# samd21_actuatorhub_pro_1_0_1b_dec2023.net
KiCad netlist of a schematic drawn in EAGLE
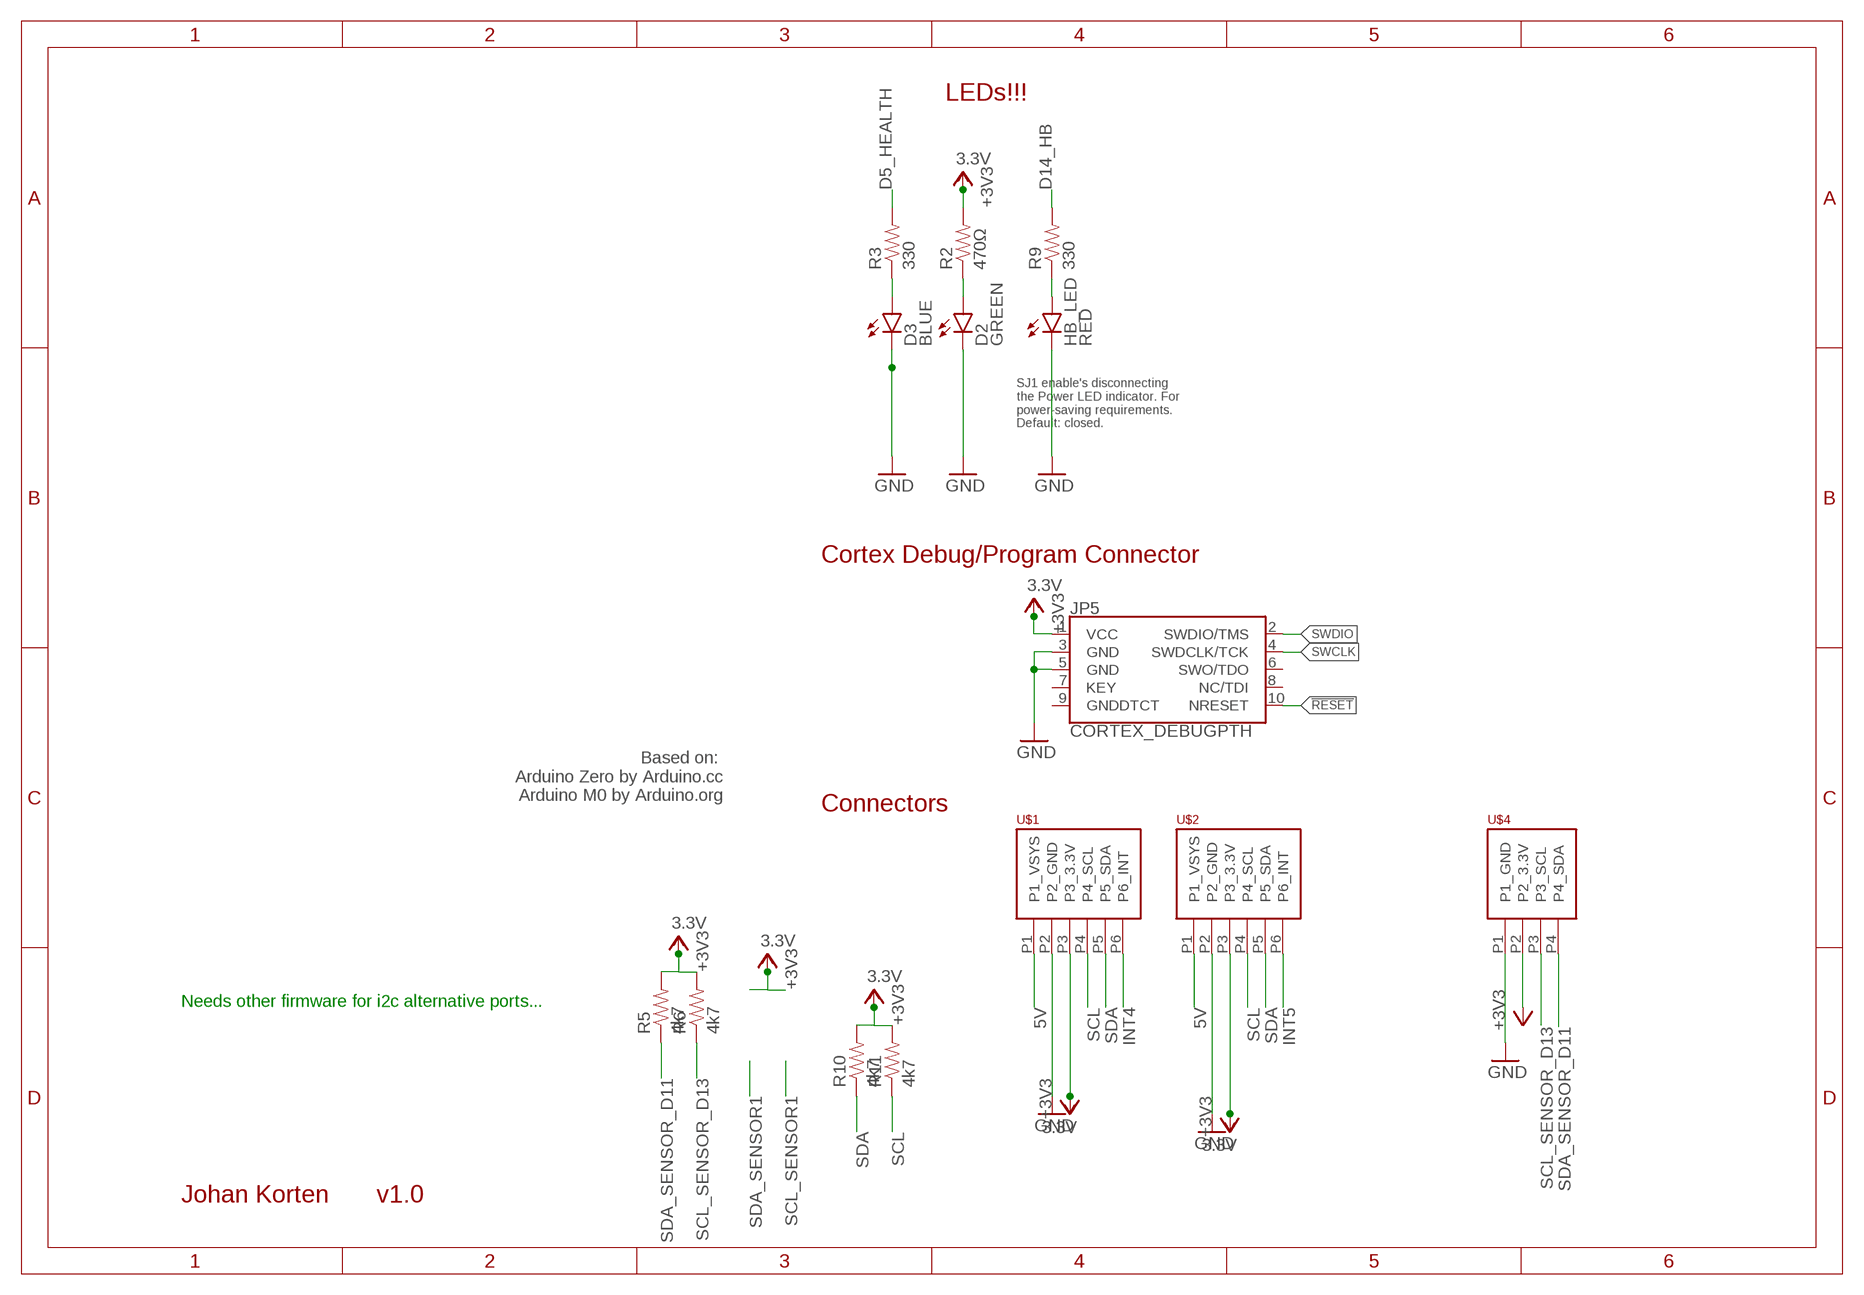
[diagram p0: schematic, sheet 1]
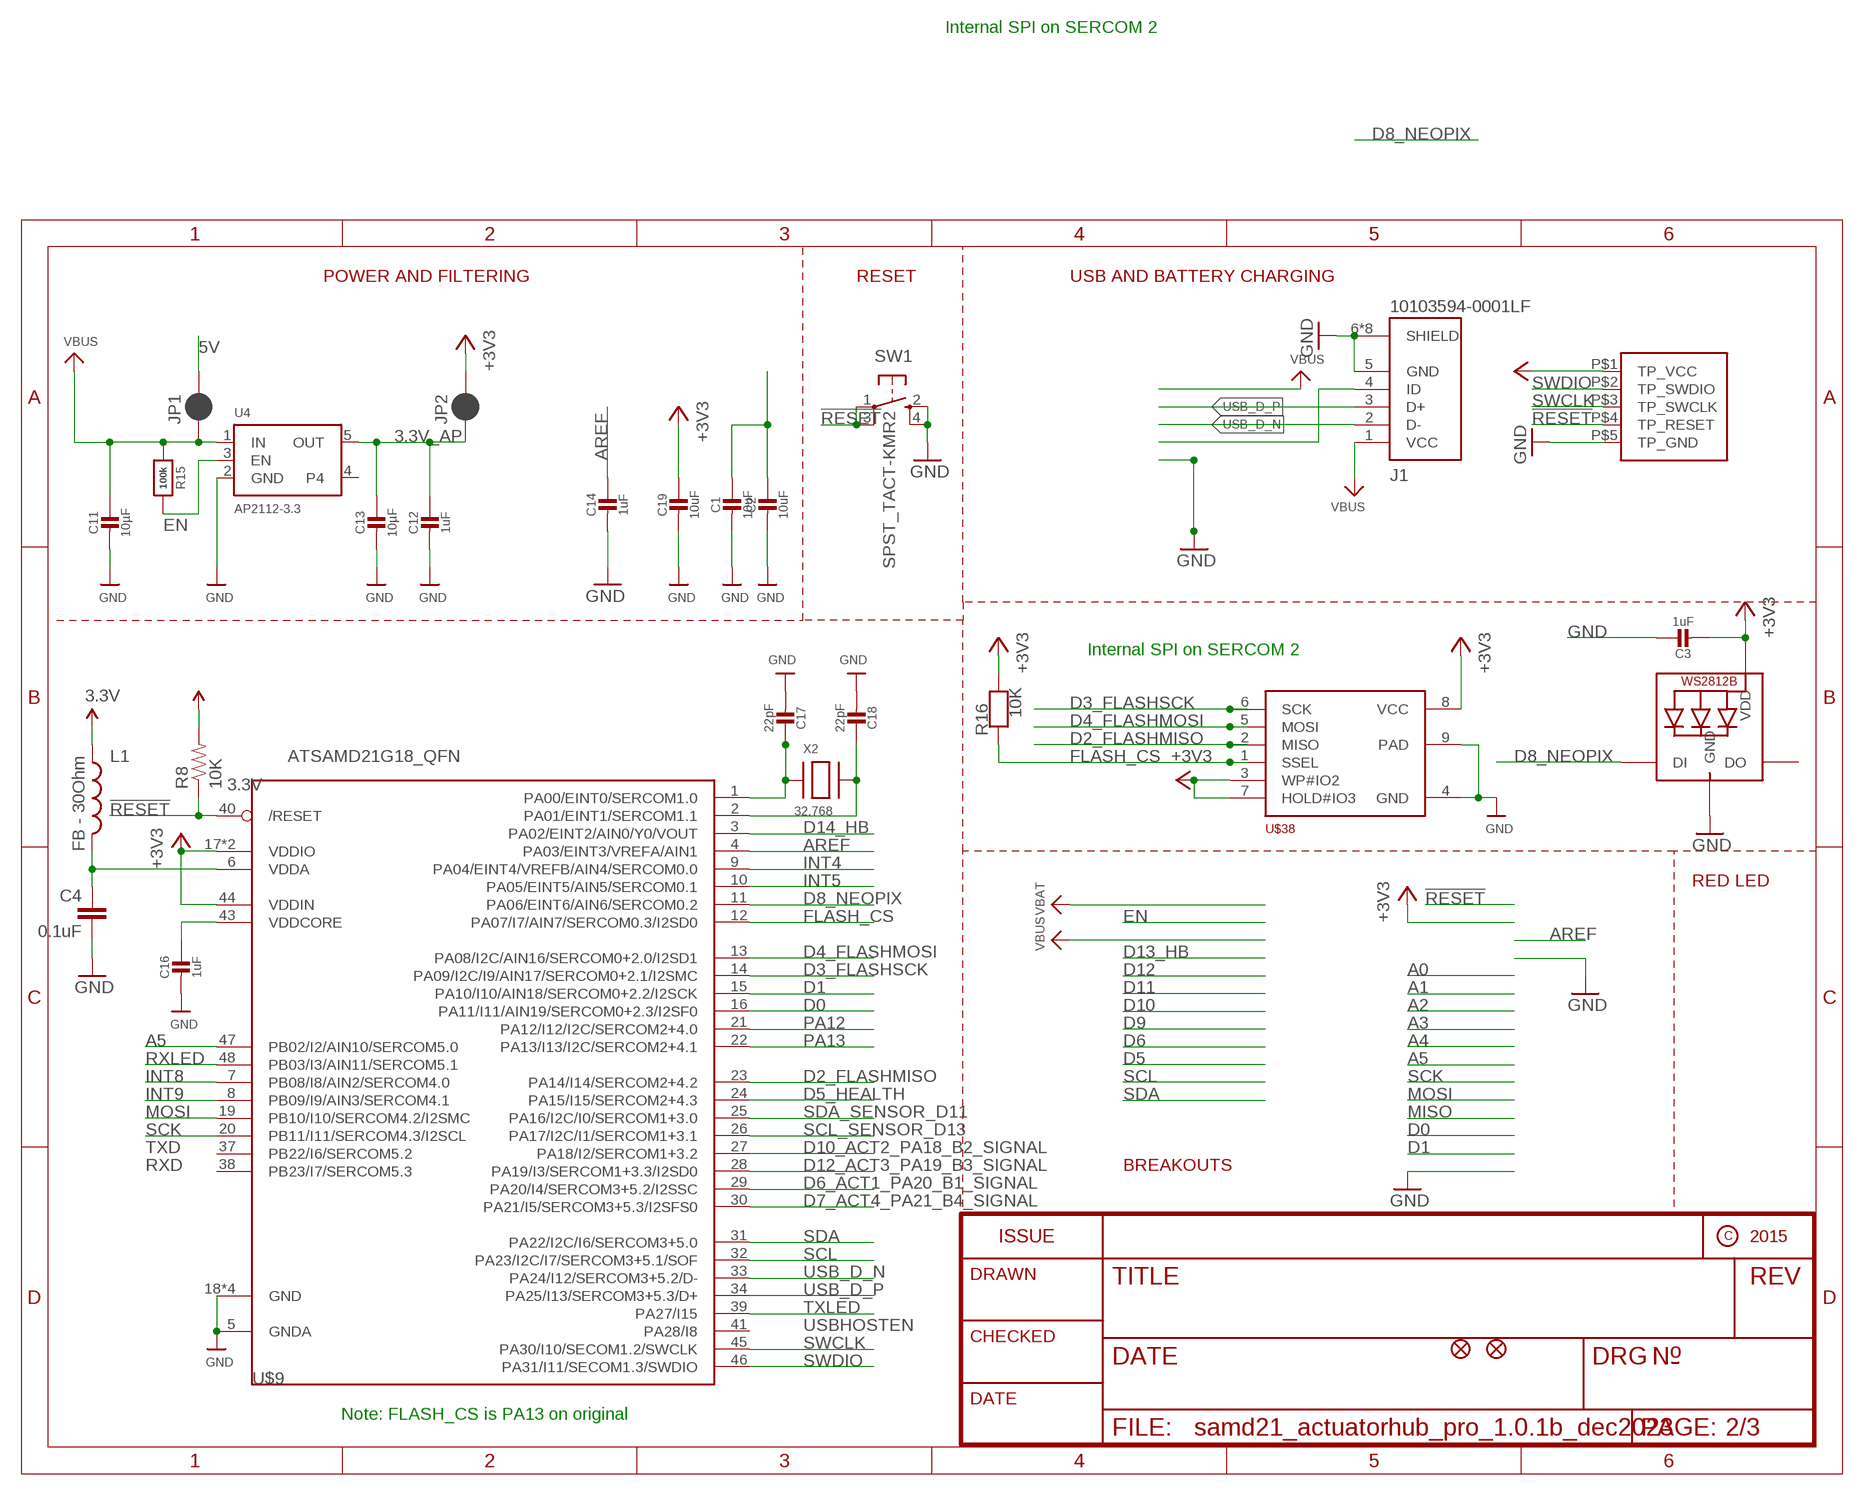
[diagram p1: schematic, sheet 2]
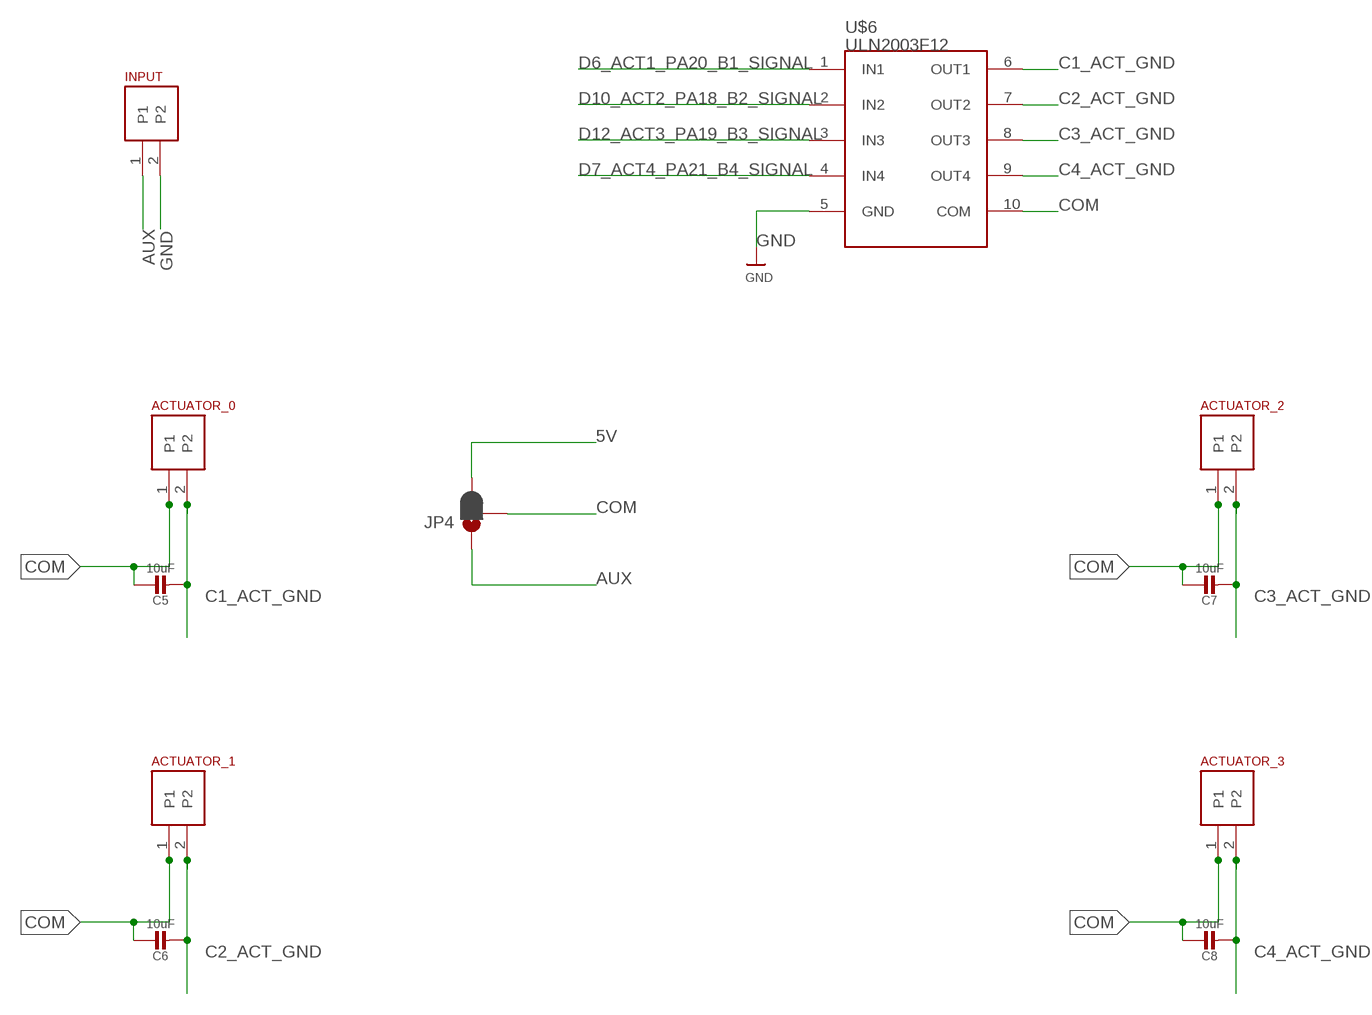
[diagram p2: schematic, sheet 3]

(export (version "E")
  (design (tool "Eeschema 10.0.6"))
  (components
    (comp (ref "ACTUATOR_0")
      (value "PHOENIX_PTSM_M2_TH")
      (footprint "eagle-import:PTSM_M2_THRHOLE")
      (libsource (lib "eagle-import") (part "PHOENIX_PTSM_M2_TH"))
    )
    (comp (ref "ACTUATOR_1")
      (value "PHOENIX_PTSM_M2_TH")
      (footprint "eagle-import:PTSM_M2_THRHOLE")
      (libsource (lib "eagle-import") (part "PHOENIX_PTSM_M2_TH"))
    )
    (comp (ref "ACTUATOR_2")
      (value "PHOENIX_PTSM_M2TH")
      (footprint "eagle-import:PTSM_M2_THRHOLE")
      (libsource (lib "eagle-import") (part "PHOENIX_PTSM_M2TH"))
    )
    (comp (ref "ACTUATOR_3")
      (value "PHOENIX_PTSM_M2TH")
      (footprint "eagle-import:PTSM_M2_THRHOLE")
      (libsource (lib "eagle-import") (part "PHOENIX_PTSM_M2TH"))
    )
    (comp (ref "C5")
      (value "10uF")
      (footprint "eagle-import:0805-NO")
      (libsource (lib "eagle-import") (part "CAP_CERAMIC0805-NOOUTLINE"))
    )
    (comp (ref "C6")
      (value "10uF")
      (footprint "eagle-import:0805-NO")
      (libsource (lib "eagle-import") (part "CAP_CERAMIC0805-NOOUTLINE"))
    )
    (comp (ref "C7")
      (value "10uF")
      (footprint "eagle-import:0805-NO")
      (libsource (lib "eagle-import") (part "CAP_CERAMIC0805-NOOUTLINE"))
    )
    (comp (ref "C8")
      (value "10uF")
      (footprint "eagle-import:0805-NO")
      (libsource (lib "eagle-import") (part "CAP_CERAMIC0805-NOOUTLINE"))
    )
    (comp (ref "INPUT")
      (value "PHOENIX_PTSM_M2_TH")
      (footprint "eagle-import:PTSM_M2_THRHOLE")
      (libsource (lib "eagle-import") (part "PHOENIX_PTSM_M2_TH"))
    )
    (comp (ref "JP4")
      (value "JUMPER-SMT_3_1-NC_PASTE_SILK")
      (footprint "eagle-import:SMT-JUMPER_3_1-NC_PASTE_SILK")
      (libsource (lib "eagle-import") (part "JUMPER-SMT_3_1-NC_PASTE_SILK"))
    )
    (comp (ref "U$6")
      (value "ULN2003F12")
      (footprint "eagle-import:U-DFN3030-10")
      (fields (field (name "MF") "Diodes Zetex"))
      (libsource (lib "eagle-import") (part "ULN2003F12"))
    )
    (comp (ref "D2")
      (value "GREEN")
      (footprint "eagle-import:LED-0603")
      (libsource (lib "eagle-import") (part "LED-RED0603"))
    )
    (comp (ref "D3")
      (value "BLUE")
      (footprint "eagle-import:LED-0603")
      (libsource (lib "eagle-import") (part "LED-BLUE0603"))
    )
    (comp (ref "HB_LED")
      (value "RED")
      (footprint "eagle-import:LED-0603")
      (libsource (lib "eagle-import") (part "LED-RED0603"))
    )
    (comp (ref "JP5")
      (value "CORTEX_DEBUGPTH")
      (footprint "eagle-import:2X5-PTH-1.27MM")
      (libsource (lib "eagle-import") (part "CORTEX_DEBUGPTH"))
    )
    (comp (ref "R2")
      (value "470Ω")
      (footprint "eagle-import:0603-RES")
      (libsource (lib "eagle-import") (part "330OHM1/10W1%(0603)"))
    )
    (comp (ref "R3")
      (value "330")
      (footprint "eagle-import:0603-RES")
      (libsource (lib "eagle-import") (part "330OHM1/10W1%(0603)"))
    )
    (comp (ref "R5")
      (value "4k7")
      (footprint "eagle-import:0603-RES")
      (libsource (lib "eagle-import") (part "330OHM1/10W1%(0603)"))
    )
    (comp (ref "R6")
      (value "4k7")
      (footprint "eagle-import:0603-RES")
      (libsource (lib "eagle-import") (part "330OHM1/10W1%(0603)"))
    )
    (comp (ref "R9")
      (value "330")
      (footprint "eagle-import:0603-RES")
      (libsource (lib "eagle-import") (part "330OHM1/10W1%(0603)"))
    )
    (comp (ref "R10")
      (value "4k7")
      (footprint "eagle-import:0603-RES")
      (libsource (lib "eagle-import") (part "330OHM1/10W1%(0603)"))
    )
    (comp (ref "R11")
      (value "4k7")
      (footprint "eagle-import:0603-RES")
      (libsource (lib "eagle-import") (part "330OHM1/10W1%(0603)"))
    )
    (comp (ref "U$1")
      (value "PHOENIX_PTSM_M6_TH_I2CPPANGLE")
      (footprint "eagle-import:PTSM_M6_THRHOLE")
      (libsource (lib "eagle-import") (part "PHOENIX_PTSM_M6_TH_I2CPPANGLE"))
    )
    (comp (ref "U$2")
      (value "PHOENIX_PTSM_M6_TH_I2CPPANGLE")
      (footprint "eagle-import:PTSM_M6_THRHOLE")
      (libsource (lib "eagle-import") (part "PHOENIX_PTSM_M6_TH_I2CPPANGLE"))
    )
    (comp (ref "U$4")
      (value "PHOENIX_PTSM_M4_THANGLE")
      (footprint "eagle-import:PTSM_M4_TH")
      (libsource (lib "eagle-import") (part "PHOENIX_PTSM_M4_THANGLE"))
    )
    (comp (ref "C1")
      (value "10uF")
      (footprint "eagle-import:0805-NO")
      (libsource (lib "eagle-import") (part "CAP_CERAMIC0805-NOOUTLINE"))
    )
    (comp (ref "C2")
      (value "10uF")
      (footprint "eagle-import:0805-NO")
      (libsource (lib "eagle-import") (part "CAP_CERAMIC0805-NOOUTLINE"))
    )
    (comp (ref "C3")
      (value "1uF")
      (footprint "eagle-import:0603-NO")
      (libsource (lib "eagle-import") (part "CAP_CERAMIC0603_NO"))
    )
    (comp (ref "C4")
      (value "0.1uF")
      (footprint "eagle-import:0402-CAP")
      (libsource (lib "eagle-import") (part "0.1UF-16V(+-10%)(0402)"))
    )
    (comp (ref "C11")
      (value "10µF")
      (footprint "eagle-import:0805-NO")
      (libsource (lib "eagle-import") (part "CAP_CERAMIC0805-NOOUTLINE"))
    )
    (comp (ref "C12")
      (value "1uF")
      (footprint "eagle-import:0603-NO")
      (libsource (lib "eagle-import") (part "CAP_CERAMIC0603_NO"))
    )
    (comp (ref "C13")
      (value "10µF")
      (footprint "eagle-import:0805-NO")
      (libsource (lib "eagle-import") (part "CAP_CERAMIC0805-NOOUTLINE"))
    )
    (comp (ref "C14")
      (value "1uF")
      (footprint "eagle-import:0603-NO")
      (libsource (lib "eagle-import") (part "CAP_CERAMIC0603_NO"))
    )
    (comp (ref "C16")
      (value "1uF")
      (footprint "eagle-import:0603-NO")
      (libsource (lib "eagle-import") (part "CAP_CERAMIC0603_NO"))
    )
    (comp (ref "C17")
      (value "22pF")
      (footprint "eagle-import:0603-NO")
      (libsource (lib "eagle-import") (part "CAP_CERAMIC0603_NO"))
    )
    (comp (ref "C18")
      (value "22pF")
      (footprint "eagle-import:0603-NO")
      (libsource (lib "eagle-import") (part "CAP_CERAMIC0603_NO"))
    )
    (comp (ref "C19")
      (value "10uF")
      (footprint "eagle-import:0805-NO")
      (libsource (lib "eagle-import") (part "CAP_CERAMIC0805-NOOUTLINE"))
    )
    (comp (ref "J1")
      (value "10103594-0001LF")
      (footprint "eagle-import:AMPHENOL_10103594-0001LF")
      (fields (field (name "MF") "AMPHENOL ICC / FCI"))
      (libsource (lib "eagle-import") (part "10103594-0001LF"))
    )
    (comp (ref "JP1")
      (value "JUMPER-SMT_2_NC_PASTE_SILK")
      (footprint "eagle-import:SMT-JUMPER_2_NC_PASTE_SILK")
      (libsource (lib "eagle-import") (part "JUMPER-SMT_2_NC_PASTE_SILK"))
    )
    (comp (ref "JP2")
      (value "JUMPER-SMT_2_NC_PASTE_SILK")
      (footprint "eagle-import:SMT-JUMPER_2_NC_PASTE_SILK")
      (libsource (lib "eagle-import") (part "JUMPER-SMT_2_NC_PASTE_SILK"))
    )
    (comp (ref "L1")
      (value "FB - 30Ohm")
      (footprint "eagle-import:0603")
      (libsource (lib "eagle-import") (part "INDUCTOR0603"))
    )
    (comp (ref "LED1")
      (value "WS2812B3535")
      (footprint "eagle-import:LED3535")
      (libsource (lib "eagle-import") (part "WS2812B3535"))
    )
    (comp (ref "R8")
      (value "10K")
      (footprint "eagle-import:0603-RES")
      (libsource (lib "eagle-import") (part "10KOHM-1/10W-1%(0603)0603"))
    )
    (comp (ref "R15")
      (value "100k")
      (footprint "eagle-import:0603-NO")
      (libsource (lib "eagle-import") (part "RESISTOR_0603_NOOUT"))
    )
    (comp (ref "R16")
      (value "10K")
      (footprint "eagle-import:0603-NO")
      (libsource (lib "eagle-import") (part "RESISTOR_0603_NOOUT"))
    )
    (comp (ref "SW1")
      (value "SPST_TACT-KMR2")
      (footprint "eagle-import:KMR2")
      (libsource (lib "eagle-import") (part "SPST_TACT-KMR2"))
    )
    (comp (ref "U$5")
      (value "HUB_TESTPINSHUBS")
      (footprint "eagle-import:TEST_PINS")
      (libsource (lib "eagle-import") (part "HUB_TESTPINSHUBS"))
    )
    (comp (ref "U$9")
      (value "ATSAMD21G18_QFN")
      (footprint "eagle-import:TQFN48_7MM")
      (libsource (lib "eagle-import") (part "ATSAMD21G_QFN"))
    )
    (comp (ref "U$34")
      (value "FIDUCIAL\"\"")
      (footprint "eagle-import:FIDUCIAL_1MM")
      (libsource (lib "eagle-import") (part "FIDUCIAL{dblquote}{dblquote}"))
    )
    (comp (ref "U$35")
      (value "FIDUCIAL\"\"")
      (footprint "eagle-import:FIDUCIAL_1MM")
      (libsource (lib "eagle-import") (part "FIDUCIAL{dblquote}{dblquote}"))
    )
    (comp (ref "U$38")
      (value "S25FL064LABNFI040")
      (footprint "eagle-import:SON80P400X400X60-9N")
      (libsource (lib "eagle-import") (part "S25FL064LABNFI040"))
    )
    (comp (ref "U4")
      (value "AP2112-3.3")
      (footprint "eagle-import:SOT23-5")
      (libsource (lib "eagle-import") (part "VREG_SOT23-5"))
    )
    (comp (ref "X2")
      (value "32.768")
      (footprint "eagle-import:XTAL3215")
      (libsource (lib "eagle-import") (part "XTAL-3.2X1.5"))
    )
  )
  (nets
    (net (code "1") (name "+3V3") (class "Default")
      (node (ref "C19") (pin "1") (pinfunction "1_1") (pintype "passive"))
      (node (ref "C3") (pin "2") (pinfunction "2_2") (pintype "passive"))
      (node (ref "JP2") (pin "2") (pinfunction "2_2") (pintype "passive"))
      (node (ref "JP5") (pin "1") (pinfunction "VCC_1") (pintype "bidirectional"))
      (node (ref "L1") (pin "1") (pinfunction "1_1") (pintype "passive"))
      (node (ref "LED1") (pin "2") (pinfunction "VDD_2") (pintype "power_in"))
      (node (ref "R10") (pin "2") (pinfunction "2_2") (pintype "passive"))
      (node (ref "R11") (pin "2") (pinfunction "2_2") (pintype "passive"))
      (node (ref "R16") (pin "2") (pinfunction "2_2") (pintype "passive"))
      (node (ref "R2") (pin "2") (pinfunction "2_2") (pintype "passive"))
      (node (ref "R5") (pin "2") (pinfunction "2_2") (pintype "passive"))
      (node (ref "R6") (pin "2") (pinfunction "2_2") (pintype "passive"))
      (node (ref "R8") (pin "2") (pinfunction "2_2") (pintype "passive"))
      (node (ref "U$1") (pin "P3") (pinfunction "P3_3.3V_P3") (pintype "power_in"))
      (node (ref "U$2") (pin "P3") (pinfunction "P3_3.3V_P3") (pintype "power_in"))
      (node (ref "U$38") (pin "3") (pinfunction "WP#IO2_3") (pintype "bidirectional"))
      (node (ref "U$38") (pin "7") (pinfunction "HOLD#IO3_7") (pintype "bidirectional"))
      (node (ref "U$38") (pin "8") (pinfunction "VCC_8") (pintype "bidirectional"))
      (node (ref "U$4") (pin "P2") (pinfunction "P2_3.3V_P2") (pintype "power_in"))
      (node (ref "U$5") (pin "P$1") (pinfunction "TP_VCC_P$1") (pintype "bidirectional"))
      (node (ref "U$9") (pin "17") (pinfunction "VDDIO_17") (pintype "power_in"))
      (node (ref "U$9") (pin "36") (pinfunction "VDDIO_36") (pintype "power_in"))
      (node (ref "U$9") (pin "44") (pinfunction "VDDIN_44") (pintype "power_in"))
    )
    (net (code "2") (name "3.3V_AP") (class "Default")
      (node (ref "C12") (pin "1") (pinfunction "1_1") (pintype "passive"))
      (node (ref "C13") (pin "1") (pinfunction "1_1") (pintype "passive"))
      (node (ref "JP2") (pin "1") (pinfunction "1_1") (pintype "passive"))
      (node (ref "U4") (pin "5") (pinfunction "OUT_5") (pintype "power_in"))
    )
    (net (code "3") (name "5V") (class "Default")
      (node (ref "C1") (pin "1") (pinfunction "1_1") (pintype "passive"))
      (node (ref "C2") (pin "1") (pinfunction "1_1") (pintype "passive"))
      (node (ref "JP1") (pin "2") (pinfunction "2_2") (pintype "passive"))
      (node (ref "JP4") (pin "3") (pinfunction "3_3") (pintype "passive"))
      (node (ref "U$1") (pin "P1") (pinfunction "P1_VSYS_P1") (pintype "power_in"))
      (node (ref "U$2") (pin "P1") (pinfunction "P1_VSYS_P1") (pintype "power_in"))
    )
    (net (code "9") (name "A5") (class "Default")
      (node (ref "U$9") (pin "47") (pinfunction "PB02/I2/AIN10/SERCOM5.0_47") (pintype "bidirectional"))
    )
    (net (code "10") (name "AREF") (class "Default")
      (node (ref "C14") (pin "1") (pinfunction "1_1") (pintype "passive"))
      (node (ref "U$9") (pin "4") (pinfunction "PA03/EINT3/VREFA/AIN1_4") (pintype "bidirectional"))
    )
    (net (code "11") (name "AUX") (class "Default")
      (node (ref "INPUT") (pin "1") (pinfunction "P1_1") (pintype "bidirectional"))
      (node (ref "JP4") (pin "1") (pinfunction "1_1") (pintype "passive"))
    )
    (net (code "12") (name "C1_ACT_GND") (class "Default")
      (node (ref "ACTUATOR_0") (pin "2") (pinfunction "P2_2") (pintype "bidirectional"))
      (node (ref "C5") (pin "2") (pinfunction "2_2") (pintype "passive"))
      (node (ref "U$6") (pin "6") (pinfunction "OUT1_6") (pintype "bidirectional"))
    )
    (net (code "13") (name "C2_ACT_GND") (class "Default")
      (node (ref "ACTUATOR_1") (pin "2") (pinfunction "P2_2") (pintype "bidirectional"))
      (node (ref "C6") (pin "2") (pinfunction "2_2") (pintype "passive"))
      (node (ref "U$6") (pin "7") (pinfunction "OUT2_7") (pintype "bidirectional"))
    )
    (net (code "14") (name "C3_ACT_GND") (class "Default")
      (node (ref "ACTUATOR_2") (pin "2") (pinfunction "P2_2") (pintype "bidirectional"))
      (node (ref "C7") (pin "2") (pinfunction "2_2") (pintype "passive"))
      (node (ref "U$6") (pin "8") (pinfunction "OUT3_8") (pintype "bidirectional"))
    )
    (net (code "15") (name "C4_ACT_GND") (class "Default")
      (node (ref "ACTUATOR_3") (pin "2") (pinfunction "P2_2") (pintype "bidirectional"))
      (node (ref "C8") (pin "2") (pinfunction "2_2") (pintype "passive"))
      (node (ref "U$6") (pin "9") (pinfunction "OUT4_9") (pintype "bidirectional"))
    )
    (net (code "16") (name "COM") (class "Default")
      (node (ref "ACTUATOR_0") (pin "1") (pinfunction "P1_1") (pintype "bidirectional"))
      (node (ref "ACTUATOR_1") (pin "1") (pinfunction "P1_1") (pintype "bidirectional"))
      (node (ref "ACTUATOR_2") (pin "1") (pinfunction "P1_1") (pintype "bidirectional"))
      (node (ref "ACTUATOR_3") (pin "1") (pinfunction "P1_1") (pintype "bidirectional"))
      (node (ref "C5") (pin "1") (pinfunction "1_1") (pintype "passive"))
      (node (ref "C6") (pin "1") (pinfunction "1_1") (pintype "passive"))
      (node (ref "C7") (pin "1") (pinfunction "1_1") (pintype "passive"))
      (node (ref "C8") (pin "1") (pinfunction "1_1") (pintype "passive"))
      (node (ref "JP4") (pin "2") (pinfunction "2_2") (pintype "passive"))
      (node (ref "U$6") (pin "10") (pinfunction "COM_10") (pintype "bidirectional"))
    )
    (net (code "17") (name "D0") (class "Default")
      (node (ref "U$9") (pin "16") (pinfunction "PA11/I11/AIN19/SERCOM0+2.3/I2SF0_16") (pintype "bidirectional"))
    )
    (net (code "18") (name "D1") (class "Default")
      (node (ref "U$9") (pin "15") (pinfunction "PA10/I10/AIN18/SERCOM0+2.2/I2SCK_15") (pintype "bidirectional"))
    )
    (net (code "19") (name "D2_FLASHMISO") (class "Default")
      (node (ref "U$38") (pin "2") (pinfunction "MISO_2") (pintype "bidirectional"))
      (node (ref "U$9") (pin "23") (pinfunction "PA14/I14/SERCOM2+4.2_23") (pintype "bidirectional"))
    )
    (net (code "20") (name "D3_FLASHSCK") (class "Default")
      (node (ref "U$38") (pin "6") (pinfunction "SCK_6") (pintype "bidirectional"))
      (node (ref "U$9") (pin "14") (pinfunction "PA09/I2C/I9/AIN17/SERCOM0+2.1/I2SMC_14") (pintype "bidirectional"))
    )
    (net (code "21") (name "D4_FLASHMOSI") (class "Default")
      (node (ref "U$38") (pin "5") (pinfunction "MOSI_5") (pintype "bidirectional"))
      (node (ref "U$9") (pin "13") (pinfunction "PA08/I2C/AIN16/SERCOM0+2.0/I2SD1_13") (pintype "bidirectional"))
    )
    (net (code "23") (name "D5_HEALTH") (class "Default")
      (node (ref "R3") (pin "2") (pinfunction "2_2") (pintype "passive"))
      (node (ref "U$9") (pin "24") (pinfunction "PA15/I15/SERCOM2+4.3_24") (pintype "bidirectional"))
    )
    (net (code "25") (name "D6_ACT1_PA20_B1_SIGNAL") (class "Default")
      (node (ref "U$6") (pin "1") (pinfunction "IN1_1") (pintype "bidirectional"))
      (node (ref "U$9") (pin "29") (pinfunction "PA20/I4/SERCOM3+5.2/I2SSC_29") (pintype "bidirectional"))
    )
    (net (code "26") (name "D7_ACT4_PA21_B4_SIGNAL") (class "Default")
      (node (ref "U$6") (pin "4") (pinfunction "IN4_4") (pintype "bidirectional"))
      (node (ref "U$9") (pin "30") (pinfunction "PA21/I5/SERCOM3+5.3/I2SFS0_30") (pintype "bidirectional"))
    )
    (net (code "27") (name "D8_NEOPIX") (class "Default")
      (node (ref "LED1") (pin "1") (pinfunction "DI_1") (pintype "input"))
      (node (ref "U$9") (pin "11") (pinfunction "PA06/EINT6/AIN6/SERCOM0.2_11") (pintype "bidirectional"))
    )
    (net (code "30") (name "D10_ACT2_PA18_B2_SIGNAL") (class "Default")
      (node (ref "U$6") (pin "2") (pinfunction "IN2_2") (pintype "bidirectional"))
      (node (ref "U$9") (pin "27") (pinfunction "PA18/I2/SERCOM1+3.2_27") (pintype "bidirectional"))
    )
    (net (code "33") (name "D12_ACT3_PA19_B3_SIGNAL") (class "Default")
      (node (ref "U$6") (pin "3") (pinfunction "IN3_3") (pintype "bidirectional"))
      (node (ref "U$9") (pin "28") (pinfunction "PA19/I3/SERCOM1+3.3/I2SD0_28") (pintype "bidirectional"))
    )
    (net (code "35") (name "D14_HB") (class "Default")
      (node (ref "R9") (pin "2") (pinfunction "2_2") (pintype "passive"))
      (node (ref "U$9") (pin "3") (pinfunction "PA02/EINT2/AIN0/Y0/VOUT_3") (pintype "bidirectional"))
    )
    (net (code "36") (name "EN") (class "Default")
      (node (ref "R15") (pin "2") (pinfunction "2_2") (pintype "passive"))
      (node (ref "U4") (pin "3") (pinfunction "EN_3") (pintype "input"))
    )
    (net (code "37") (name "FLASH_CS") (class "Default")
      (node (ref "R16") (pin "1") (pinfunction "1_1") (pintype "passive"))
      (node (ref "U$38") (pin "1") (pinfunction "SSEL_1") (pintype "bidirectional"))
      (node (ref "U$9") (pin "12") (pinfunction "PA07/I7/AIN7/SERCOM0.3/I2SD0_12") (pintype "bidirectional"))
    )
    (net (code "38") (name "GND") (class "Default")
      (node (ref "C1") (pin "2") (pinfunction "2_2") (pintype "passive"))
      (node (ref "C11") (pin "2") (pinfunction "2_2") (pintype "passive"))
      (node (ref "C12") (pin "2") (pinfunction "2_2") (pintype "passive"))
      (node (ref "C13") (pin "2") (pinfunction "2_2") (pintype "passive"))
      (node (ref "C14") (pin "2") (pinfunction "2_2") (pintype "passive"))
      (node (ref "C16") (pin "2") (pinfunction "2_2") (pintype "passive"))
      (node (ref "C17") (pin "2") (pinfunction "2_2") (pintype "passive"))
      (node (ref "C18") (pin "2") (pinfunction "2_2") (pintype "passive"))
      (node (ref "C19") (pin "2") (pinfunction "2_2") (pintype "passive"))
      (node (ref "C2") (pin "2") (pinfunction "2_2") (pintype "passive"))
      (node (ref "C3") (pin "1") (pinfunction "1_1") (pintype "passive"))
      (node (ref "C4") (pin "2") (pinfunction "2_2") (pintype "passive"))
      (node (ref "D2") (pin "C") (pinfunction "C_C") (pintype "passive"))
      (node (ref "D3") (pin "C") (pinfunction "C_C") (pintype "passive"))
      (node (ref "HB_LED") (pin "C") (pinfunction "C_C") (pintype "passive"))
      (node (ref "INPUT") (pin "2") (pinfunction "P2_2") (pintype "bidirectional"))
      (node (ref "J1") (pin "10") (pinfunction "SHIELD_10") (pintype "passive"))
      (node (ref "J1") (pin "11") (pinfunction "SHIELD_11") (pintype "passive"))
      (node (ref "J1") (pin "5") (pinfunction "GND_5") (pintype "power_in"))
      (node (ref "J1") (pin "6") (pinfunction "SHIELD_6") (pintype "passive"))
      (node (ref "J1") (pin "7") (pinfunction "SHIELD_7") (pintype "passive"))
      (node (ref "J1") (pin "8") (pinfunction "SHIELD_8") (pintype "passive"))
      (node (ref "J1") (pin "9") (pinfunction "SHIELD_9") (pintype "passive"))
      (node (ref "J1") (pin "S1") (pinfunction "SHIELD_S1") (pintype "passive"))
      (node (ref "J1") (pin "S2") (pinfunction "SHIELD_S2") (pintype "passive"))
      (node (ref "JP5") (pin "3") (pinfunction "GND_3") (pintype "bidirectional"))
      (node (ref "JP5") (pin "5") (pinfunction "GND_5") (pintype "bidirectional"))
      (node (ref "LED1") (pin "4") (pinfunction "GND_4") (pintype "power_in"))
      (node (ref "SW1") (pin "2") (pinfunction "S_2") (pintype "passive"))
      (node (ref "SW1") (pin "4") (pinfunction "S1_4") (pintype "passive"))
      (node (ref "U$1") (pin "P2") (pinfunction "P2_GND_P2") (pintype "power_in"))
      (node (ref "U$2") (pin "P2") (pinfunction "P2_GND_P2") (pintype "power_in"))
      (node (ref "U$38") (pin "4") (pinfunction "GND_4") (pintype "bidirectional"))
      (node (ref "U$38") (pin "9") (pinfunction "PAD_9") (pintype "bidirectional"))
      (node (ref "U$4") (pin "P1") (pinfunction "P1_GND_P1") (pintype "power_in"))
      (node (ref "U$5") (pin "P$5") (pinfunction "TP_GND_P$5") (pintype "bidirectional"))
      (node (ref "U$6") (pin "5") (pinfunction "GND_5") (pintype "bidirectional"))
      (node (ref "U$9") (pin "18") (pinfunction "GND_18") (pintype "power_in"))
      (node (ref "U$9") (pin "35") (pinfunction "GND_35") (pintype "power_in"))
      (node (ref "U$9") (pin "42") (pinfunction "GND_42") (pintype "power_in"))
      (node (ref "U$9") (pin "5") (pinfunction "GNDA_5") (pintype "power_in"))
      (node (ref "U$9") (pin "THERMAL") (pinfunction "GND_THERMAL") (pintype "power_in"))
      (node (ref "U4") (pin "2") (pinfunction "GND_2") (pintype "power_in"))
    )
    (net (code "39") (name "INT4") (class "Default")
      (node (ref "U$1") (pin "P6") (pinfunction "P6_INT_P6") (pintype "power_in"))
      (node (ref "U$9") (pin "9") (pinfunction "PA04/EINT4/VREFB/AIN4/SERCOM0.0_9") (pintype "bidirectional"))
    )
    (net (code "40") (name "INT5") (class "Default")
      (node (ref "U$2") (pin "P6") (pinfunction "P6_INT_P6") (pintype "power_in"))
      (node (ref "U$9") (pin "10") (pinfunction "PA05/EINT5/AIN5/SERCOM0.1_10") (pintype "bidirectional"))
    )
    (net (code "41") (name "INT8") (class "Default")
      (node (ref "U$9") (pin "7") (pinfunction "PB08/I8/AIN2/SERCOM4.0_7") (pintype "bidirectional"))
    )
    (net (code "42") (name "INT9") (class "Default")
      (node (ref "U$9") (pin "8") (pinfunction "PB09/I9/AIN3/SERCOM4.1_8") (pintype "bidirectional"))
    )
    (net (code "44") (name "MOSI") (class "Default")
      (node (ref "U$9") (pin "19") (pinfunction "PB10/I10/SERCOM4.2/I2SMC_19") (pintype "bidirectional"))
    )
    (net (code "45") (name "Net-(D2-PadA)") (class "Default")
      (node (ref "D2") (pin "A") (pinfunction "A_A") (pintype "passive"))
      (node (ref "R2") (pin "1") (pinfunction "1_1") (pintype "passive"))
    )
    (net (code "46") (name "Net-(D3-PadA)") (class "Default")
      (node (ref "D3") (pin "A") (pinfunction "A_A") (pintype "passive"))
      (node (ref "R3") (pin "1") (pinfunction "1_1") (pintype "passive"))
    )
    (net (code "47") (name "Net-(HB_LED-PadA)") (class "Default")
      (node (ref "HB_LED") (pin "A") (pinfunction "A_A") (pintype "passive"))
      (node (ref "R9") (pin "1") (pinfunction "1_1") (pintype "passive"))
    )
    (net (code "48") (name "Net-(U$9-PA00{slash}EINT0{slash}SERCOM1.0)") (class "Default")
      (node (ref "C17") (pin "1") (pinfunction "1_1") (pintype "passive"))
      (node (ref "U$9") (pin "1") (pinfunction "PA00/EINT0/SERCOM1.0_1") (pintype "bidirectional"))
      (node (ref "X2") (pin "P$1") (pinfunction "P$1_P$1") (pintype "bidirectional"))
    )
    (net (code "49") (name "Net-(U$9-PA01{slash}EINT1{slash}SERCOM1.1)") (class "Default")
      (node (ref "C18") (pin "1") (pinfunction "1_1") (pintype "passive"))
      (node (ref "U$9") (pin "2") (pinfunction "PA01/EINT1/SERCOM1.1_2") (pintype "bidirectional"))
      (node (ref "X2") (pin "P$2") (pinfunction "P$2_P$2") (pintype "bidirectional"))
    )
    (net (code "50") (name "Net-(U$9-VDDA)") (class "Default")
      (node (ref "C4") (pin "1") (pinfunction "1_1") (pintype "passive"))
      (node (ref "L1") (pin "2") (pinfunction "2_2") (pintype "passive"))
      (node (ref "U$9") (pin "6") (pinfunction "VDDA_6") (pintype "power_in"))
    )
    (net (code "51") (name "Net-(U$9-VDDCORE)") (class "Default")
      (node (ref "C16") (pin "1") (pinfunction "1_1") (pintype "passive"))
      (node (ref "U$9") (pin "43") (pinfunction "VDDCORE_43") (pintype "power_in"))
    )
    (net (code "52") (name "PA12") (class "Default")
      (node (ref "U$9") (pin "21") (pinfunction "PA12/I12/I2C/SERCOM2+4.0_21") (pintype "bidirectional"))
    )
    (net (code "53") (name "PA13") (class "Default")
      (node (ref "U$9") (pin "22") (pinfunction "PA13/I13/I2C/SERCOM2+4.1_22") (pintype "bidirectional"))
    )
    (net (code "54") (name "RXLED") (class "Default")
      (node (ref "U$9") (pin "48") (pinfunction "PB03/I3/AIN11/SERCOM5.1_48") (pintype "bidirectional"))
    )
    (net (code "55") (name "SCK") (class "Default")
      (node (ref "U$9") (pin "20") (pinfunction "PB11/I11/SERCOM4.3/I2SCL_20") (pintype "bidirectional"))
    )
    (net (code "56") (name "SCL") (class "Default")
      (node (ref "R11") (pin "1") (pinfunction "1_1") (pintype "passive"))
      (node (ref "U$1") (pin "P4") (pinfunction "P4_SCL_P4") (pintype "bidirectional"))
      (node (ref "U$2") (pin "P4") (pinfunction "P4_SCL_P4") (pintype "bidirectional"))
      (node (ref "U$9") (pin "32") (pinfunction "PA23/I2C/I7/SERCOM3+5.1/SOF_32") (pintype "bidirectional"))
    )
    (net (code "58") (name "SCL_SENSOR_D13") (class "Default")
      (node (ref "R6") (pin "1") (pinfunction "1_1") (pintype "passive"))
      (node (ref "U$4") (pin "P3") (pinfunction "P3_SCL_P3") (pintype "bidirectional"))
      (node (ref "U$9") (pin "26") (pinfunction "PA17/I2C/I1/SERCOM1+3.1_26") (pintype "bidirectional"))
    )
    (net (code "59") (name "SDA") (class "Default")
      (node (ref "R10") (pin "1") (pinfunction "1_1") (pintype "passive"))
      (node (ref "U$1") (pin "P5") (pinfunction "P5_SDA_P5") (pintype "bidirectional"))
      (node (ref "U$2") (pin "P5") (pinfunction "P5_SDA_P5") (pintype "bidirectional"))
      (node (ref "U$9") (pin "31") (pinfunction "PA22/I2C/I6/SERCOM3+5.0_31") (pintype "bidirectional"))
    )
    (net (code "61") (name "SDA_SENSOR_D11") (class "Default")
      (node (ref "R5") (pin "1") (pinfunction "1_1") (pintype "passive"))
      (node (ref "U$4") (pin "P4") (pinfunction "P4_SDA_P4") (pintype "bidirectional"))
      (node (ref "U$9") (pin "25") (pinfunction "PA16/I2C/I0/SERCOM1+3.0_25") (pintype "bidirectional"))
    )
    (net (code "62") (name "SWCLK") (class "Default")
      (node (ref "JP5") (pin "4") (pinfunction "SWDCLK/TCK_4") (pintype "bidirectional"))
      (node (ref "U$5") (pin "P$3") (pinfunction "TP_SWCLK_P$3") (pintype "bidirectional"))
      (node (ref "U$9") (pin "45") (pinfunction "PA30/I10/SECOM1.2/SWCLK_45") (pintype "bidirectional"))
    )
    (net (code "63") (name "SWDIO") (class "Default")
      (node (ref "JP5") (pin "2") (pinfunction "SWDIO/TMS_2") (pintype "bidirectional"))
      (node (ref "U$5") (pin "P$2") (pinfunction "TP_SWDIO_P$2") (pintype "bidirectional"))
      (node (ref "U$9") (pin "46") (pinfunction "PA31/I11/SECOM1.3/SWDIO_46") (pintype "bidirectional"))
    )
    (net (code "64") (name "TXLED") (class "Default")
      (node (ref "U$9") (pin "39") (pinfunction "PA27/I15_39") (pintype "bidirectional"))
    )
    (net (code "65") (name "USB_D_N") (class "Default")
      (node (ref "J1") (pin "2") (pinfunction "D-_2") (pintype "bidirectional"))
      (node (ref "U$9") (pin "33") (pinfunction "PA24/I12/SERCOM3+5.2/D-_33") (pintype "bidirectional"))
    )
    (net (code "66") (name "USB_D_P") (class "Default")
      (node (ref "J1") (pin "3") (pinfunction "D+_3") (pintype "bidirectional"))
      (node (ref "U$9") (pin "34") (pinfunction "PA25/I13/SERCOM3+5.3/D+_34") (pintype "bidirectional"))
    )
    (net (code "68") (name "VBUS") (class "Default")
      (node (ref "C11") (pin "1") (pinfunction "1_1") (pintype "passive"))
      (node (ref "J1") (pin "1") (pinfunction "VCC_1") (pintype "power_in"))
      (node (ref "JP1") (pin "1") (pinfunction "1_1") (pintype "passive"))
      (node (ref "R15") (pin "1") (pinfunction "1_1") (pintype "passive"))
      (node (ref "U4") (pin "1") (pinfunction "IN_1") (pintype "power_in"))
    )
    (net (code "69") (name "unconnected-(J1-ID-Pad4)") (class "Default")
      (node (ref "J1") (pin "4") (pinfunction "ID_4") (pintype "bidirectional"))
    )
    (net (code "70") (name "unconnected-(JP5-GNDDTCT-Pad9)") (class "Default")
      (node (ref "JP5") (pin "9") (pinfunction "GNDDTCT_9") (pintype "bidirectional"))
    )
    (net (code "71") (name "unconnected-(JP5-KEY-Pad7)") (class "Default")
      (node (ref "JP5") (pin "7") (pinfunction "KEY_7") (pintype "bidirectional"))
    )
    (net (code "72") (name "unconnected-(JP5-NC{slash}TDI-Pad8)") (class "Default")
      (node (ref "JP5") (pin "8") (pinfunction "NC/TDI_8") (pintype "bidirectional"))
    )
    (net (code "73") (name "unconnected-(JP5-SWO{slash}TDO-Pad6)") (class "Default")
      (node (ref "JP5") (pin "6") (pinfunction "SWO/TDO_6") (pintype "bidirectional"))
    )
    (net (code "74") (name "unconnected-(LED1-DO-Pad3)") (class "Default")
      (node (ref "LED1") (pin "3") (pinfunction "DO_3") (pintype "output"))
    )
    (net (code "75") (name "unconnected-(U$9-PA28{slash}I8-Pad41)") (class "Default")
      (node (ref "U$9") (pin "41") (pinfunction "PA28/I8_41") (pintype "bidirectional"))
    )
    (net (code "76") (name "unconnected-(U$9-PB22{slash}I6{slash}SERCOM5.2-Pad37)") (class "Default")
      (node (ref "U$9") (pin "37") (pinfunction "PB22/I6/SERCOM5.2_37") (pintype "bidirectional"))
    )
    (net (code "77") (name "unconnected-(U$9-PB23{slash}I7{slash}SERCOM5.3-Pad38)") (class "Default")
      (node (ref "U$9") (pin "38") (pinfunction "PB23/I7/SERCOM5.3_38") (pintype "bidirectional"))
    )
    (net (code "78") (name "unconnected-(U4-P4-Pad4)") (class "Default")
      (node (ref "U4") (pin "4") (pinfunction "P4_4") (pintype "bidirectional"))
    )
    (net (code "79") (name "~{RESET}") (class "Default")
      (node (ref "JP5") (pin "10") (pinfunction "NRESET_10") (pintype "bidirectional"))
      (node (ref "R8") (pin "1") (pinfunction "1_1") (pintype "passive"))
      (node (ref "SW1") (pin "1") (pinfunction "P_1") (pintype "passive"))
      (node (ref "SW1") (pin "3") (pinfunction "P1_3") (pintype "passive"))
      (node (ref "U$5") (pin "P$4") (pinfunction "TP_RESET_P$4") (pintype "bidirectional"))
      (node (ref "U$9") (pin "40") (pinfunction "/RESET_40") (pintype "bidirectional"))
    )
  )
)
